# Microcontroller.net
KiCad netlist of a schematic drawn in Altium Designer
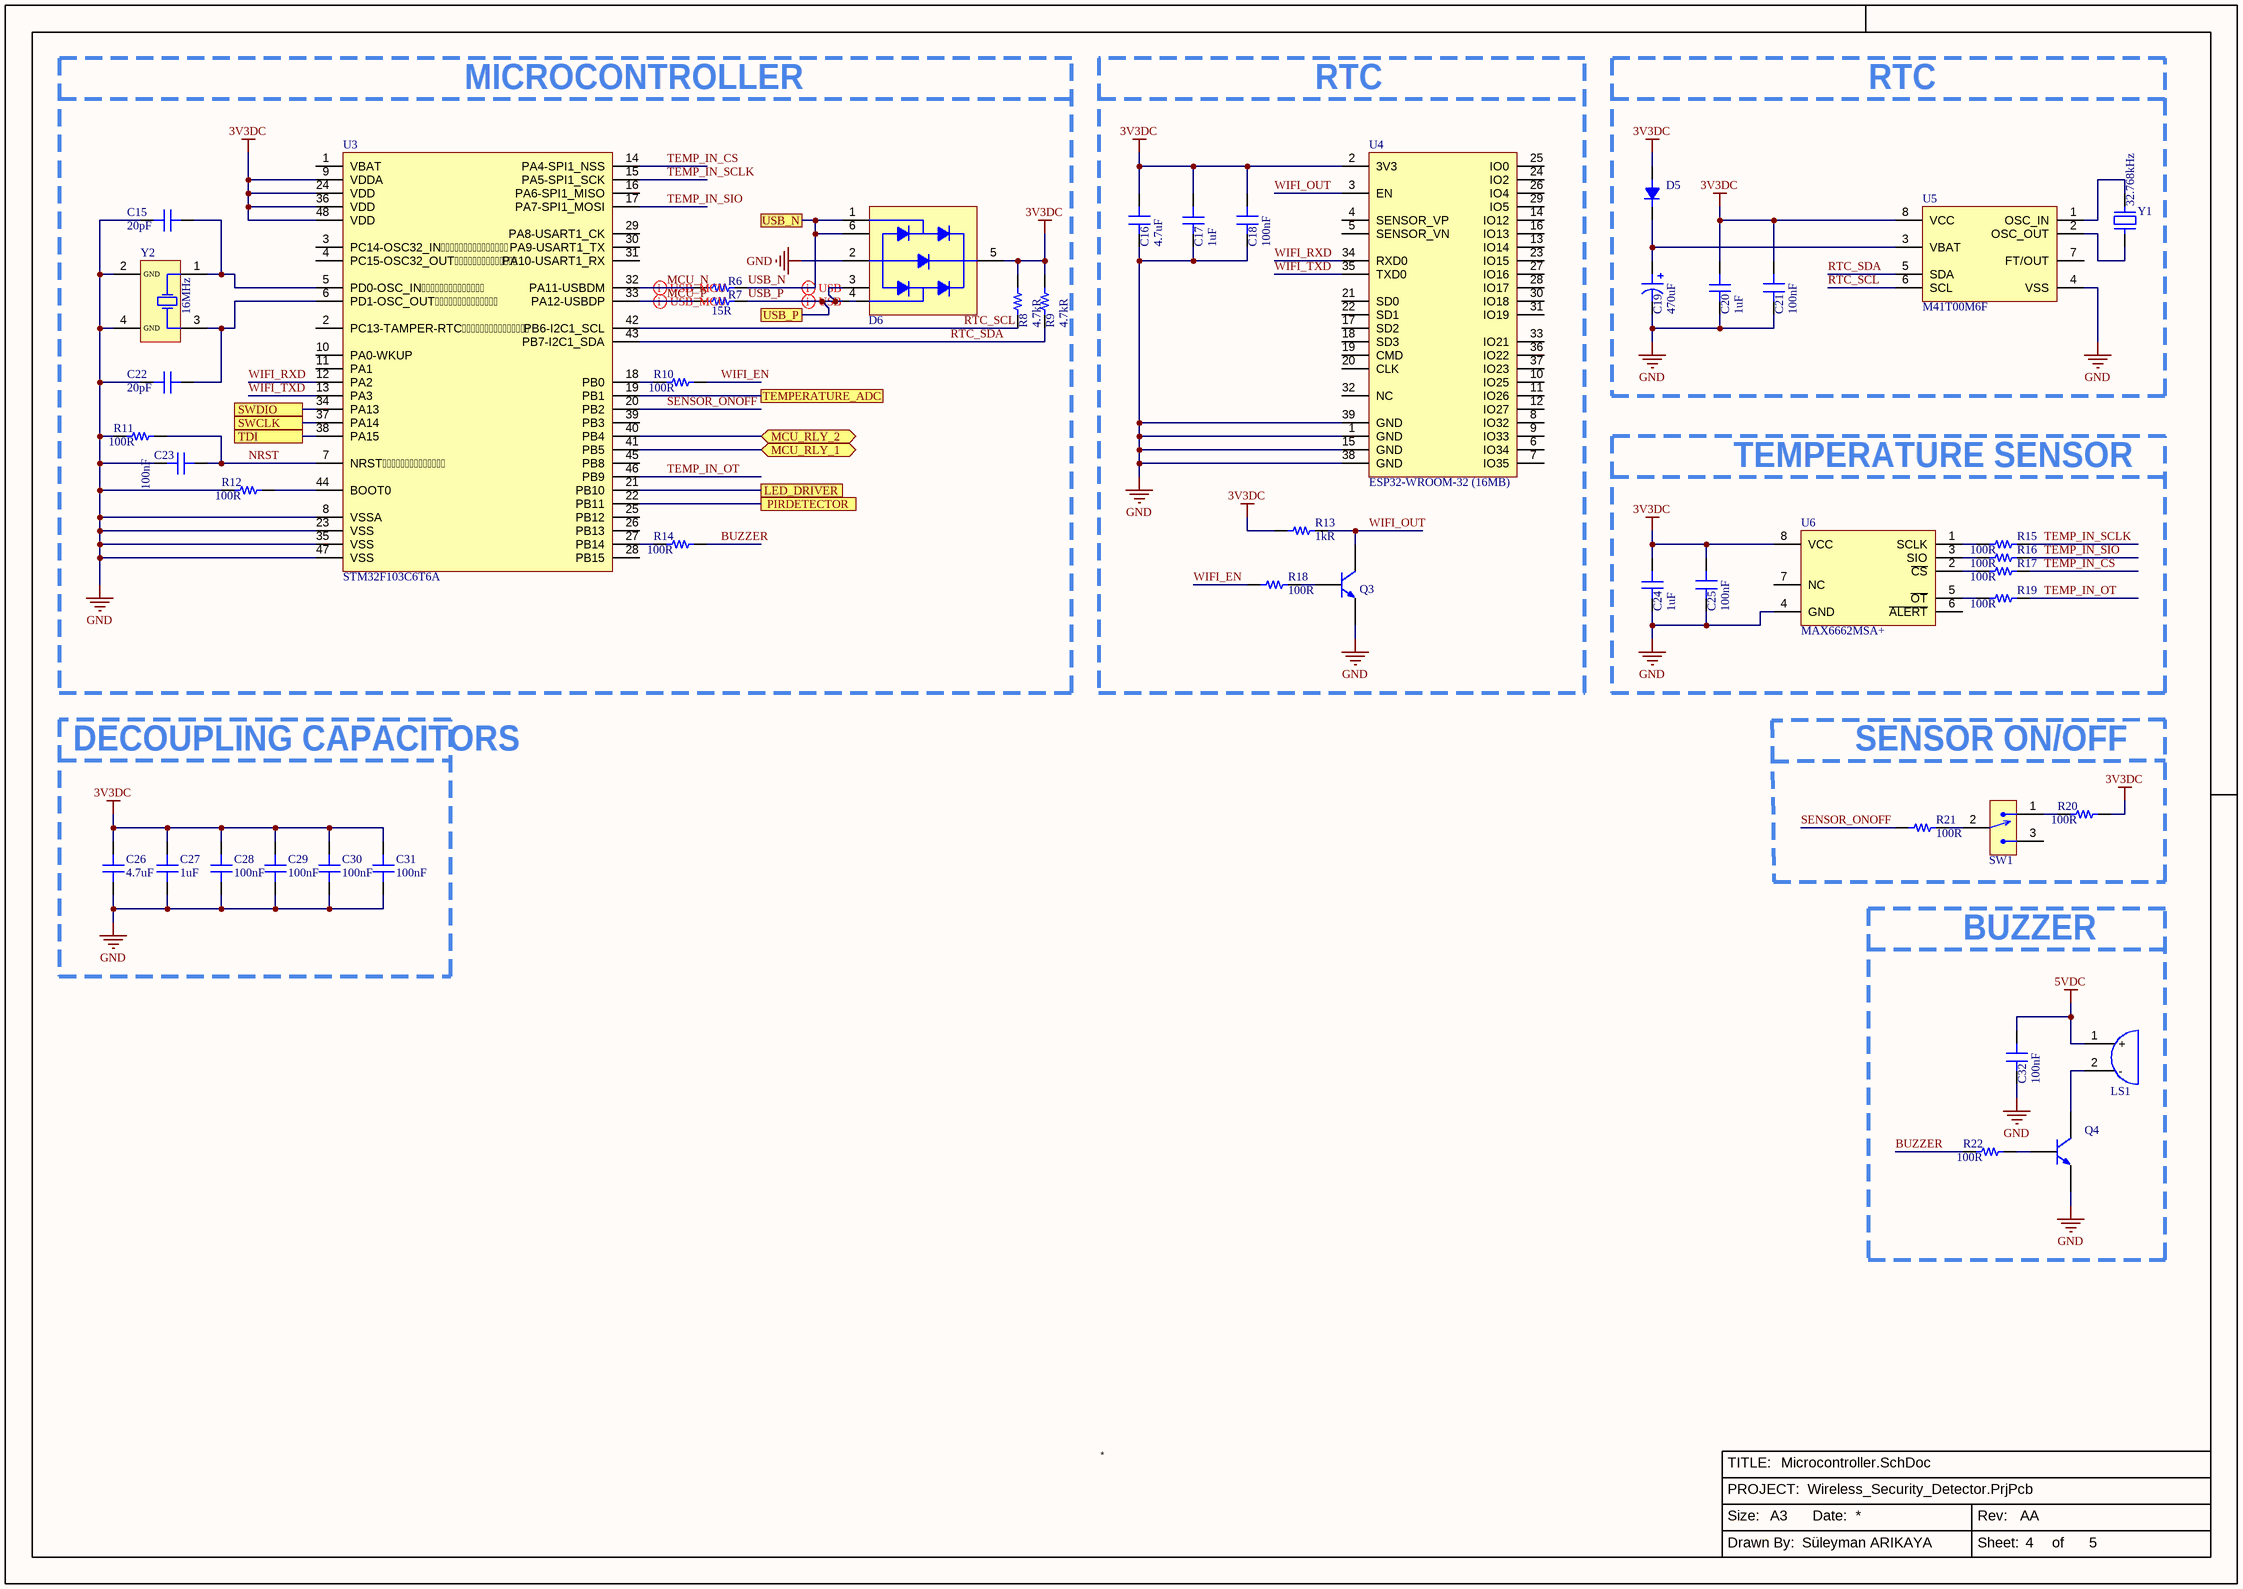
[diagram p0: Microcontroller.SchDoc]

(export (version "E")
  (design (tool "Eeschema 10.0.6"))
  (components
    (comp (ref "C15")
      (value "CL10C200JB8NNNC")
      (footprint "C0603_CER")
      (description "CAP CER 20pF %5 50V C0G/NP0 0603 SMD")
      (fields
        (field (name "MANUFACTURER") "Samsung")
        (field (name "TOLERANCE") "5%")
        (field (name "CAPACITANCE") "20pF")
        (field (name "DESIGNED BY") "Süleyman ARIKAYA")
      )
      (libsource (lib "Arikaya_Lib") (part "CAP CER 20pF 0603"))
    )
    (comp (ref "C16")
      (value "CL21A475KAQNNNE")
      (footprint "C0805_CER")
      (description "CAP CER 4.7uF %10 25V X5R 0805 SMD")
      (fields
        (field (name "MANUFACTURER") "Samsung")
        (field (name "TOLERANCE") "10%")
        (field (name "CAPACITANCE") "4.7uF")
        (field (name "DESIGNED BY") "Süleyman ARIKAYA")
      )
      (libsource (lib "Arikaya_Lib") (part "CAP CER 4.7uF 0805"))
    )
    (comp (ref "C17")
      (value "CL21B105KBFNNNE")
      (footprint "C0805_CER")
      (description "CAP CER 1uF %10 50V X7R 0805 SMD")
      (fields
        (field (name "MANUFACTURER") "Samsung")
        (field (name "TOLERANCE") "10%")
        (field (name "CAPACITANCE") "1uF")
        (field (name "DESIGNED BY") "Süleyman ARIKAYA")
      )
      (libsource (lib "Arikaya_Lib") (part "CAP CER 1uF 0805"))
    )
    (comp (ref "C18")
      (value "CL21B104KBCNNNC")
      (footprint "C0805_CER")
      (description "CAP CER 100nF %10 50V X7R 0805 SMD")
      (fields
        (field (name "MANUFACTURER") "Samsung")
        (field (name "TOLERANCE") "10%")
        (field (name "CAPACITANCE") "100nF")
        (field (name "DESIGNED BY") "Süleyman ARIKAYA")
      )
      (libsource (lib "Arikaya_Lib") (part "CAP CER 100nF 0805"))
    )
    (comp (ref "C19")
      (value "ESH477M050AH4AA")
      (footprint "CAP_RADIAL_D10_P5")
      (description "CAP ALUM 470UF 20% 50V RADIAL")
      (fields
        (field (name "MANUFACTURER") "KEMET")
        (field (name "TOLERANCE") "20%")
        (field (name "CAPACITANCE") "470uF")
        (field (name "DESIGNED BY") "Süleyman ARIKAYA")
      )
      (libsource (lib "Arikaya_Lib") (part "CAP ALU ELEC 470uF 50V"))
    )
    (comp (ref "C20")
      (value "CL21B105KBFNNNE")
      (footprint "C0805_CER")
      (description "CAP CER 1uF %10 50V X7R 0805 SMD")
      (fields
        (field (name "MANUFACTURER") "Samsung")
        (field (name "TOLERANCE") "10%")
        (field (name "CAPACITANCE") "1uF")
        (field (name "DESIGNED BY") "Süleyman ARIKAYA")
      )
      (libsource (lib "Arikaya_Lib") (part "CAP CER 1uF 0805"))
    )
    (comp (ref "C21")
      (value "CL21B104KBCNNNC")
      (footprint "C0805_CER")
      (description "CAP CER 100nF %10 50V X7R 0805 SMD")
      (fields
        (field (name "MANUFACTURER") "Samsung")
        (field (name "TOLERANCE") "10%")
        (field (name "CAPACITANCE") "100nF")
        (field (name "DESIGNED BY") "Süleyman ARIKAYA")
      )
      (libsource (lib "Arikaya_Lib") (part "CAP CER 100nF 0805"))
    )
    (comp (ref "C22")
      (value "CL10C200JB8NNNC")
      (footprint "C0603_CER")
      (description "CAP CER 20pF %5 50V C0G/NP0 0603 SMD")
      (fields
        (field (name "MANUFACTURER") "Samsung")
        (field (name "TOLERANCE") "5%")
        (field (name "CAPACITANCE") "20pF")
        (field (name "DESIGNED BY") "Süleyman ARIKAYA")
      )
      (libsource (lib "Arikaya_Lib") (part "CAP CER 20pF 0603"))
    )
    (comp (ref "C23")
      (value "C0603C104K5RAC7411")
      (footprint "C0603_CER")
      (description "CAP CER 100nF %10 50V 0603 SMD")
      (fields
        (field (name "MANUFACTURER") "KEMET")
        (field (name "TOLERANCE") "10%")
        (field (name "CAPACITANCE") "100nF")
        (field (name "DESIGNED BY") "Süleyman ARIKAYA")
      )
      (libsource (lib "Arikaya_Lib") (part "CAP CER 100nF 0603"))
    )
    (comp (ref "C24")
      (value "CL21B105KBFNNNE")
      (footprint "C0805_CER")
      (description "CAP CER 1uF %10 50V X7R 0805 SMD")
      (fields
        (field (name "MANUFACTURER") "Samsung")
        (field (name "TOLERANCE") "10%")
        (field (name "CAPACITANCE") "1uF")
        (field (name "DESIGNED BY") "Süleyman ARIKAYA")
      )
      (libsource (lib "Arikaya_Lib") (part "CAP CER 1uF 0805"))
    )
    (comp (ref "C25")
      (value "CL21B104KBCNNNC")
      (footprint "C0805_CER")
      (description "CAP CER 100nF %10 50V X7R 0805 SMD")
      (fields
        (field (name "MANUFACTURER") "Samsung")
        (field (name "TOLERANCE") "10%")
        (field (name "CAPACITANCE") "100nF")
        (field (name "DESIGNED BY") "Süleyman ARIKAYA")
      )
      (libsource (lib "Arikaya_Lib") (part "CAP CER 100nF 0805"))
    )
    (comp (ref "C26")
      (value "CL21A475KAQNNNE")
      (footprint "C0805_CER")
      (description "CAP CER 4.7uF %10 25V X5R 0805 SMD")
      (fields
        (field (name "MANUFACTURER") "Samsung")
        (field (name "TOLERANCE") "10%")
        (field (name "CAPACITANCE") "4.7uF")
        (field (name "DESIGNED BY") "Süleyman ARIKAYA")
      )
      (libsource (lib "") (part "CAP CER 4.7uF 0805_1"))
    )
    (comp (ref "C27")
      (value "CL21B105KBFNNNE")
      (footprint "C0805_CER")
      (description "CAP CER 1uF %10 50V X7R 0805 SMD")
      (fields
        (field (name "MANUFACTURER") "Samsung")
        (field (name "TOLERANCE") "10%")
        (field (name "CAPACITANCE") "1uF")
        (field (name "DESIGNED BY") "Süleyman ARIKAYA")
      )
      (libsource (lib "Arikaya_Lib") (part "CAP CER 1uF 0805"))
    )
    (comp (ref "C28")
      (value "C0603C104K5RAC7411")
      (footprint "C0603_CER")
      (description "CAP CER 100nF %10 50V 0603 SMD")
      (fields
        (field (name "MANUFACTURER") "KEMET")
        (field (name "TOLERANCE") "10%")
        (field (name "CAPACITANCE") "100nF")
        (field (name "DESIGNED BY") "Süleyman ARIKAYA")
      )
      (libsource (lib "Arikaya_Lib") (part "CAP CER 100nF 0603"))
    )
    (comp (ref "C29")
      (value "C0603C104K5RAC7411")
      (footprint "C0603_CER")
      (description "CAP CER 100nF %10 50V 0603 SMD")
      (fields
        (field (name "MANUFACTURER") "KEMET")
        (field (name "TOLERANCE") "10%")
        (field (name "CAPACITANCE") "100nF")
        (field (name "DESIGNED BY") "Süleyman ARIKAYA")
      )
      (libsource (lib "Arikaya_Lib") (part "CAP CER 100nF 0603"))
    )
    (comp (ref "C30")
      (value "C0603C104K5RAC7411")
      (footprint "C0603_CER")
      (description "CAP CER 100nF %10 50V 0603 SMD")
      (fields
        (field (name "MANUFACTURER") "KEMET")
        (field (name "TOLERANCE") "10%")
        (field (name "CAPACITANCE") "100nF")
        (field (name "DESIGNED BY") "Süleyman ARIKAYA")
      )
      (libsource (lib "Arikaya_Lib") (part "CAP CER 100nF 0603"))
    )
    (comp (ref "C31")
      (value "C0603C104K5RAC7411")
      (footprint "C0603_CER")
      (description "CAP CER 100nF %10 50V 0603 SMD")
      (fields
        (field (name "MANUFACTURER") "KEMET")
        (field (name "TOLERANCE") "10%")
        (field (name "CAPACITANCE") "100nF")
        (field (name "DESIGNED BY") "Süleyman ARIKAYA")
      )
      (libsource (lib "Arikaya_Lib") (part "CAP CER 100nF 0603"))
    )
    (comp (ref "C32")
      (value "CL21B104KBCNNNC")
      (footprint "C0805_CER")
      (description "CAP CER 100nF %10 50V X7R 0805 SMD")
      (fields
        (field (name "MANUFACTURER") "Samsung")
        (field (name "TOLERANCE") "10%")
        (field (name "CAPACITANCE") "100nF")
        (field (name "DESIGNED BY") "Süleyman ARIKAYA")
      )
      (libsource (lib "Arikaya_Lib") (part "CAP CER 100nF 0805"))
    )
    (comp (ref "D5")
      (value "1N4148WS")
      (footprint "SOD-323F")
      (description "Diode Standard 75 V 150mA Surface Mount SOD-323F VR=75V IF=150mA Trr=4ns P=200mW")
      (fields
        (field (name "MANUFACTURER") "ON Semiconductor / Fairchild")
        (field (name "DESIGNED BY") "Süleyman ARIKAYA")
      )
      (libsource (lib "Arikaya_Lib") (part "1N4148WS"))
    )
    (comp (ref "D6")
      (value "USBLC6-2SC6")
      (footprint "SOT23-6L")
      (description "TVS DIODE 5.25V 17VC SOT23-6L")
      (fields
        (field (name "MANUFACTURER") "STMicroelectronics")
        (field (name "DESIGNED BY") "Süleyman ARIKAYA")
      )
      (libsource (lib "Arikaya_Lib") (part "USB Protection TVS"))
    )
    (comp (ref "LS1")
      (value "CMI-9605IC-0580T")
      (footprint "CMI-9605IC-0580T")
      (description "Buzzers Indicator, Internally Driven Magnetic 5 V 30mA 2.7kHz 80dB @ 5V, 10cm Through Hole PC Pins")
      (fields
        (field (name "MANUFACTURER") "CUI")
        (field (name "MANUFACTURER PART NUMBER") "CMI-9605-0580T")
        (field (name "DESIGNED BY") "Süleyman ARIKAYA")
      )
      (libsource (lib "Arikaya_Lib") (part "CMI-9605IC-0580T"))
    )
    (comp (ref "Q3")
      (value "MMBT3904-7-F")
      (footprint "SOT-23F")
      (description "NPN Ic=200mA Vceo=40V hfe=100~300 fT=310MHz P=300mW SOT-23")
      (fields (field (name "MANUFACTURER") "Diodes Zetex") (field (name "DESIGNED BY") "Süleyman ARIKAYA"))
      (libsource (lib "Arikaya_Lib") (part "MMBT3904-7-F"))
    )
    (comp (ref "Q4")
      (value "MMBT3904-7-F")
      (footprint "SOT-23F")
      (description "NPN Ic=200mA Vceo=40V hfe=100~300 fT=310MHz P=300mW SOT-23")
      (fields (field (name "MANUFACTURER") "Diodes Zetex") (field (name "DESIGNED BY") "Süleyman ARIKAYA"))
      (libsource (lib "Arikaya_Lib") (part "MMBT3904-7-F"))
    )
    (comp (ref "R6")
      (value "RC0603JR-0715RL")
      (footprint "R0603")
      (description "RES 15 OHM 5% 1/10W 0603")
      (fields
        (field (name "MANUFACTURER") "Yageo")
        (field (name "TOLERANCE") "5%")
        (field (name "DESIGNED BY") "Süleyman ARIKAYA")
      )
      (libsource (lib "Arikaya_Lib") (part "RES 15 OHM 0603"))
    )
    (comp (ref "R7")
      (value "RC0603JR-0715RL")
      (footprint "R0603")
      (description "RES 15 OHM 5% 1/10W 0603")
      (fields
        (field (name "MANUFACTURER") "Yageo")
        (field (name "TOLERANCE") "5%")
        (field (name "RESISTANCE") "15R")
        (field (name "DESIGNED BY") "Süleyman ARIKAYA")
      )
      (libsource (lib "Arikaya_Lib") (part "RES 15 OHM 0603"))
    )
    (comp (ref "R8")
      (value "RC0603JR-074K7L")
      (footprint "R0603")
      (description "RES 4.7K OHM 5% 1/10W 0603")
      (fields
        (field (name "MANUFACTURER") "Yageo")
        (field (name "TOLERANCE") "5%")
        (field (name "RESISTANCE") "4.7kR")
        (field (name "DESIGNED BY") "Süleyman ARIKAYA")
      )
      (libsource (lib "Arikaya_Lib") (part "RES 4.7K OHM 0603"))
    )
    (comp (ref "R9")
      (value "RC0603JR-074K7L")
      (footprint "R0603")
      (description "RES 4.7K OHM 5% 1/10W 0603")
      (fields
        (field (name "MANUFACTURER") "Yageo")
        (field (name "TOLERANCE") "5%")
        (field (name "RESISTANCE") "4.7kR")
        (field (name "DESIGNED BY") "Süleyman ARIKAYA")
      )
      (libsource (lib "Arikaya_Lib") (part "RES 4.7K OHM 0603"))
    )
    (comp (ref "R10")
      (value "RC0603JR-07100RL")
      (footprint "R0603")
      (description "RES 100 OHM 5% 1/10W 0603")
      (fields
        (field (name "MANUFACTURER") "Yageo")
        (field (name "TOLERANCE") "5%")
        (field (name "RESISTANCE") "100R")
        (field (name "DESIGNED BY") "Süleyman ARIKAYA")
      )
      (libsource (lib "Arikaya_Lib") (part "RES 100 OHM 0603"))
    )
    (comp (ref "R11")
      (value "RC0603JR-07100RL")
      (footprint "R0603")
      (description "RES 100 OHM 5% 1/10W 0603")
      (fields
        (field (name "MANUFACTURER") "Yageo")
        (field (name "TOLERANCE") "5%")
        (field (name "RESISTANCE") "100R")
        (field (name "DESIGNED BY") "Süleyman ARIKAYA")
      )
      (libsource (lib "Arikaya_Lib") (part "RES 100 OHM 0603"))
    )
    (comp (ref "R12")
      (value "RC0603JR-07100RL")
      (footprint "R0603")
      (description "RES 100 OHM 5% 1/10W 0603")
      (fields
        (field (name "MANUFACTURER") "Yageo")
        (field (name "TOLERANCE") "5%")
        (field (name "RESISTANCE") "100R")
        (field (name "DESIGNED BY") "Süleyman ARIKAYA")
      )
      (libsource (lib "Arikaya_Lib") (part "RES 100 OHM 0603"))
    )
    (comp (ref "R13")
      (value "RC0603FR-071KL")
      (footprint "R0603")
      (description "RES SMD 1K OHM 1% 1/10W 0603")
      (fields
        (field (name "MANUFACTURER") "Yageo")
        (field (name "TOLERANCE") "1%")
        (field (name "RESISTANCE") "1kR")
        (field (name "DESIGNED BY") "Süleyman ARIKAYA")
      )
      (libsource (lib "Arikaya_Lib") (part "RES 1K OHM 0603"))
    )
    (comp (ref "R14")
      (value "RC0603JR-07100RL")
      (footprint "R0603")
      (description "RES 100 OHM 5% 1/10W 0603")
      (fields
        (field (name "MANUFACTURER") "Yageo")
        (field (name "TOLERANCE") "5%")
        (field (name "RESISTANCE") "100R")
        (field (name "DESIGNED BY") "Süleyman ARIKAYA")
      )
      (libsource (lib "Arikaya_Lib") (part "RES 100 OHM 0603"))
    )
    (comp (ref "R15")
      (value "RC0603JR-07100RL")
      (footprint "R0603")
      (description "RES 100 OHM 5% 1/10W 0603")
      (fields
        (field (name "MANUFACTURER") "Yageo")
        (field (name "TOLERANCE") "5%")
        (field (name "RESISTANCE") "100R")
        (field (name "DESIGNED BY") "Süleyman ARIKAYA")
      )
      (libsource (lib "Arikaya_Lib") (part "RES 100 OHM 0603"))
    )
    (comp (ref "R16")
      (value "RC0603JR-07100RL")
      (footprint "R0603")
      (description "RES 100 OHM 5% 1/10W 0603")
      (fields
        (field (name "MANUFACTURER") "Yageo")
        (field (name "TOLERANCE") "5%")
        (field (name "RESISTANCE") "100R")
        (field (name "DESIGNED BY") "Süleyman ARIKAYA")
      )
      (libsource (lib "Arikaya_Lib") (part "RES 100 OHM 0603"))
    )
    (comp (ref "R17")
      (value "RC0603JR-07100RL")
      (footprint "R0603")
      (description "RES 100 OHM 5% 1/10W 0603")
      (fields
        (field (name "MANUFACTURER") "Yageo")
        (field (name "TOLERANCE") "5%")
        (field (name "RESISTANCE") "100R")
        (field (name "DESIGNED BY") "Süleyman ARIKAYA")
      )
      (libsource (lib "Arikaya_Lib") (part "RES 100 OHM 0603"))
    )
    (comp (ref "R18")
      (value "RC0603JR-07100RL")
      (footprint "R0603")
      (description "RES 100 OHM 5% 1/10W 0603")
      (fields
        (field (name "MANUFACTURER") "Yageo")
        (field (name "TOLERANCE") "5%")
        (field (name "RESISTANCE") "100R")
        (field (name "DESIGNED BY") "Süleyman ARIKAYA")
      )
      (libsource (lib "Arikaya_Lib") (part "RES 100 OHM 0603"))
    )
    (comp (ref "R19")
      (value "RC0603JR-07100RL")
      (footprint "R0603")
      (description "RES 100 OHM 5% 1/10W 0603")
      (fields
        (field (name "MANUFACTURER") "Yageo")
        (field (name "TOLERANCE") "5%")
        (field (name "RESISTANCE") "100R")
        (field (name "DESIGNED BY") "Süleyman ARIKAYA")
      )
      (libsource (lib "Arikaya_Lib") (part "RES 100 OHM 0603"))
    )
    (comp (ref "R20")
      (value "RC0603JR-07100RL")
      (footprint "R0603")
      (description "RES 100 OHM 5% 1/10W 0603")
      (fields
        (field (name "MANUFACTURER") "Yageo")
        (field (name "TOLERANCE") "5%")
        (field (name "RESISTANCE") "100R")
        (field (name "DESIGNED BY") "Süleyman ARIKAYA")
      )
      (libsource (lib "Arikaya_Lib") (part "RES 100 OHM 0603"))
    )
    (comp (ref "R21")
      (value "RC0603JR-07100RL")
      (footprint "R0603")
      (description "RES 100 OHM 5% 1/10W 0603")
      (fields
        (field (name "MANUFACTURER") "Yageo")
        (field (name "TOLERANCE") "5%")
        (field (name "RESISTANCE") "100R")
        (field (name "DESIGNED BY") "Süleyman ARIKAYA")
      )
      (libsource (lib "Arikaya_Lib") (part "RES 100 OHM 0603"))
    )
    (comp (ref "R22")
      (value "RC0603JR-07100RL")
      (footprint "R0603")
      (description "RES 100 OHM 5% 1/10W 0603")
      (fields
        (field (name "MANUFACTURER") "Yageo")
        (field (name "TOLERANCE") "5%")
        (field (name "RESISTANCE") "100R")
        (field (name "DESIGNED BY") "Süleyman ARIKAYA")
      )
      (libsource (lib "Arikaya_Lib") (part "RES 100 OHM 0603"))
    )
    (comp (ref "SW1")
      (value "EG1215AA")
      (footprint "EG1215AA")
      (description "Slide Switch, SPDT, 0.025A, 24V, SMD")
      (fields
        (field (name "MANUFACTURER") "E-Switch")
        (field (name "TOLERANCE") "4.95%")
        (field (name "DESIGNED BY") "Süleyman ARIKAYA")
      )
      (libsource (lib "Arikaya_Lib") (part "EG1215AA"))
    )
    (comp (ref "U3")
      (value "STM32F103C6T6A")
      (footprint "LQFP-48")
      (description "MCU 32-bit STM32F ARM Cortex M3 RISC 32KB Flash 2.5V/3.3V 48-Pin LQFP Tray")
      (fields
        (field (name "MANUFACTURER") "STMicroelectronics")
        (field (name "DESIGNED BY") "Süleyman ARIKAYA")
      )
      (libsource (lib "Arikaya_Lib") (part "STM32F103C6T6A"))
    )
    (comp (ref "U4")
      (value "ESP32-WROOM-32 (16MB)")
      (footprint "ESP32-WROOM-32")
      (fields
        (field (name "MANUFACTURER") "Espressif Systems")
        (field (name "MANUFACTURER PART NUMBER") "ESP32-WROOM-32E(M113EH3200PH3Q0)")
        (field (name "DESIGNED BY") "Süleyman ARIKAYA")
      )
      (libsource (lib "Arikaya_Lib") (part "ESP32-WROOM-32 (16MB)"))
    )
    (comp (ref "U5")
      (value "M41T00M6F")
      (footprint "SOIC8")
      (description "Real-time Clocks Clock/Calendar I2C, 2-Wire Serial 70uA @ 2V ~ 5.5V SOIC-8_150mil RoHS")
      (fields
        (field (name "MANUFACTURER") "STMicroelectronics")
        (field (name "DESIGNED BY") "Süleyman ARIKAYA")
      )
      (libsource (lib "Arikaya_Lib") (part "M41T00M6F"))
    )
    (comp (ref "U6")
      (value "MAX6662MSA+")
      (footprint "SOIC8")
      (description "Temp Sensor Digital Serial (3-Wire, SPI) 8-Pin SOIC N Tube")
      (fields (field (name "MANUFACTURER") "Maxim") (field (name "DESIGNED BY") "Süleyman ARIKAYA"))
      (libsource (lib "Arikaya_Lib") (part "MAX6662MSA+"))
    )
    (comp (ref "Y1")
      (value "ABS05-32.768KHZ-T")
      (footprint "ABS05")
      (description "CRYSTAL 32.7680KHZ 12.5PF SMD")
      (fields
        (field (name "MANUFACTURER") "Abracon")
        (field (name "TOLERANCE") "20ppm")
        (field (name "FREQUENCY") "32.768kHz")
        (field (name "DESIGNED BY") "Süleyman ARIKAYA")
      )
      (libsource (lib "Arikaya_Lib") (part "CRYSTAL 32768kHz"))
    )
    (comp (ref "Y2")
      (value "ECS-160-20-30B-TR")
      (footprint "ECS CRYSTAL 16MHZ")
      (description "CRYSTAL 16.0000MHZ 20PF SMD")
      (fields
        (field (name "MANUFACTURER") "ECS International")
        (field (name "TOLERANCE") "50ppm")
        (field (name "FREQUENCY") "16MHz")
        (field (name "DESIGNED BY") "Süleyman ARIKAYA")
      )
      (libsource (lib "Arikaya_Lib") (part "CRYSTAL 16MHz 20pF"))
    )
  )
  (nets
    (net (code "1") (name "/BUZZER") (class "Default")
      (node (ref "R14") (pin "2") (pinfunction "2_2") (pintype "passive"))
      (node (ref "R22") (pin "1") (pinfunction "1_1") (pintype "passive"))
    )
    (net (code "2") (name "/LED_DRIVER") (class "Default")
      (node (ref "U3") (pin "21") (pinfunction "PB10_21") (pintype "passive"))
    )
    (net (code "3") (name "/MCU_N") (class "Default")
      (node (ref "R6") (pin "1") (pinfunction "1_1") (pintype "passive"))
      (node (ref "U3") (pin "32") (pinfunction "PA11-USBDM_32") (pintype "passive"))
    )
    (net (code "4") (name "/MCU_P") (class "Default")
      (node (ref "R7") (pin "1") (pinfunction "1_1") (pintype "passive"))
      (node (ref "U3") (pin "33") (pinfunction "PA12-USBDP_33") (pintype "passive"))
    )
    (net (code "5") (name "/MCU_RLY_1") (class "Default")
      (node (ref "U3") (pin "41") (pinfunction "PB5_41") (pintype "passive"))
    )
    (net (code "6") (name "/MCU_RLY_2") (class "Default")
      (node (ref "U3") (pin "40") (pinfunction "PB4_40") (pintype "passive"))
    )
    (net (code "7") (name "/NRST") (class "Default")
      (node (ref "C23") (pin "2") (pinfunction "2_2") (pintype "passive"))
      (node (ref "R11") (pin "2") (pinfunction "2_2") (pintype "passive"))
      (node (ref "U3") (pin "7") (pinfunction "NRST_7") (pintype "passive"))
    )
    (net (code "8") (name "/PIRDETECTOR") (class "Default")
      (node (ref "U3") (pin "22") (pinfunction "PB11_22") (pintype "passive"))
    )
    (net (code "9") (name "/RTC_SCL") (class "Default")
      (node (ref "R8") (pin "1") (pinfunction "1_1") (pintype "passive"))
      (node (ref "U3") (pin "42") (pinfunction "PB6-I2C1_SCL_42") (pintype "passive"))
      (node (ref "U5") (pin "6") (pinfunction "SCL_6") (pintype "passive"))
    )
    (net (code "10") (name "/RTC_SDA") (class "Default")
      (node (ref "R9") (pin "2") (pinfunction "2_2") (pintype "passive"))
      (node (ref "U3") (pin "43") (pinfunction "PB7-I2C1_SDA_43") (pintype "passive"))
      (node (ref "U5") (pin "5") (pinfunction "SDA_5") (pintype "passive"))
    )
    (net (code "11") (name "/SENSOR_ONOFF") (class "Default")
      (node (ref "R21") (pin "1") (pinfunction "1_1") (pintype "passive"))
      (node (ref "U3") (pin "20") (pinfunction "PB2_20") (pintype "passive"))
    )
    (net (code "12") (name "/SWCLK") (class "Default")
      (node (ref "U3") (pin "37") (pinfunction "PA14_37") (pintype "passive"))
    )
    (net (code "13") (name "/SWDIO") (class "Default")
      (node (ref "U3") (pin "34") (pinfunction "PA13_34") (pintype "passive"))
    )
    (net (code "14") (name "/TDI") (class "Default")
      (node (ref "U3") (pin "38") (pinfunction "PA15_38") (pintype "passive"))
    )
    (net (code "15") (name "/TEMPERATURE_ADC") (class "Default")
      (node (ref "U3") (pin "19") (pinfunction "PB1_19") (pintype "passive"))
    )
    (net (code "16") (name "/TEMP_IN_CS") (class "Default")
      (node (ref "R17") (pin "2") (pinfunction "2_2") (pintype "passive"))
      (node (ref "U3") (pin "14") (pinfunction "PA4-SPI1_NSS_14") (pintype "passive"))
    )
    (net (code "17") (name "/TEMP_IN_OT") (class "Default")
      (node (ref "R19") (pin "2") (pinfunction "2_2") (pintype "passive"))
      (node (ref "U3") (pin "46") (pinfunction "PB9_46") (pintype "passive"))
    )
    (net (code "18") (name "/TEMP_IN_SCLK") (class "Default")
      (node (ref "R15") (pin "2") (pinfunction "2_2") (pintype "passive"))
      (node (ref "U3") (pin "15") (pinfunction "PA5-SPI1_SCK_15") (pintype "passive"))
    )
    (net (code "19") (name "/TEMP_IN_SIO") (class "Default")
      (node (ref "R16") (pin "2") (pinfunction "2_2") (pintype "passive"))
      (node (ref "U3") (pin "17") (pinfunction "PA7-SPI1_MOSI_17") (pintype "passive"))
    )
    (net (code "20") (name "/USB_N") (class "Default")
      (node (ref "D6") (pin "1") (pinfunction "I/O1_1") (pintype "passive"))
      (node (ref "D6") (pin "6") (pinfunction "I/O1_6") (pintype "passive"))
      (node (ref "R6") (pin "2") (pinfunction "2_2") (pintype "passive"))
    )
    (net (code "21") (name "/USB_P") (class "Default")
      (node (ref "D6") (pin "3") (pinfunction "I/O2_3") (pintype "passive"))
      (node (ref "D6") (pin "4") (pinfunction "I/O2_4") (pintype "passive"))
      (node (ref "R7") (pin "2") (pinfunction "2_2") (pintype "passive"))
    )
    (net (code "22") (name "/WIFI_EN") (class "Default")
      (node (ref "R10") (pin "2") (pinfunction "2_2") (pintype "passive"))
      (node (ref "R18") (pin "1") (pinfunction "1_1") (pintype "passive"))
    )
    (net (code "23") (name "/WIFI_OUT") (class "Default")
      (node (ref "Q3") (pin "3") (pinfunction "C_3") (pintype "passive"))
      (node (ref "R13") (pin "2") (pinfunction "2_2") (pintype "passive"))
      (node (ref "U4") (pin "3") (pinfunction "EN_3") (pintype "passive"))
    )
    (net (code "24") (name "/WIFI_RXD") (class "Default")
      (node (ref "U3") (pin "12") (pinfunction "PA2_12") (pintype "passive"))
      (node (ref "U4") (pin "34") (pinfunction "RXD0_34") (pintype "passive"))
    )
    (net (code "25") (name "/WIFI_TXD") (class "Default")
      (node (ref "U3") (pin "13") (pinfunction "PA3_13") (pintype "passive"))
      (node (ref "U4") (pin "35") (pinfunction "TXD0_35") (pintype "passive"))
    )
    (net (code "26") (name "3V3DC") (class "Default")
      (node (ref "C16") (pin "2") (pinfunction "2_2") (pintype "passive"))
      (node (ref "C17") (pin "2") (pinfunction "2_2") (pintype "passive"))
      (node (ref "C18") (pin "2") (pinfunction "2_2") (pintype "passive"))
      (node (ref "C20") (pin "2") (pinfunction "2_2") (pintype "passive"))
      (node (ref "C21") (pin "2") (pinfunction "2_2") (pintype "passive"))
      (node (ref "C24") (pin "2") (pinfunction "2_2") (pintype "passive"))
      (node (ref "C25") (pin "2") (pinfunction "2_2") (pintype "passive"))
      (node (ref "C26") (pin "2") (pinfunction "2_2") (pintype "passive"))
      (node (ref "C27") (pin "2") (pinfunction "2_2") (pintype "passive"))
      (node (ref "C28") (pin "2") (pinfunction "2_2") (pintype "passive"))
      (node (ref "C29") (pin "2") (pinfunction "2_2") (pintype "passive"))
      (node (ref "C30") (pin "2") (pinfunction "2_2") (pintype "passive"))
      (node (ref "C31") (pin "2") (pinfunction "2_2") (pintype "passive"))
      (node (ref "D5") (pin "A") (pinfunction "A_A") (pintype "passive"))
      (node (ref "D6") (pin "5") (pinfunction "VBUS_5") (pintype "passive"))
      (node (ref "R13") (pin "1") (pinfunction "1_1") (pintype "passive"))
      (node (ref "R20") (pin "2") (pinfunction "2_2") (pintype "passive"))
      (node (ref "R8") (pin "2") (pinfunction "2_2") (pintype "passive"))
      (node (ref "R9") (pin "1") (pinfunction "1_1") (pintype "passive"))
      (node (ref "U3") (pin "24") (pinfunction "VDD_24") (pintype "passive"))
      (node (ref "U3") (pin "36") (pinfunction "VDD_36") (pintype "passive"))
      (node (ref "U3") (pin "48") (pinfunction "VDD_48") (pintype "passive"))
      (node (ref "U3") (pin "9") (pinfunction "VDDA_9") (pintype "passive"))
      (node (ref "U4") (pin "2") (pinfunction "3V3_2") (pintype "passive"))
      (node (ref "U5") (pin "8") (pinfunction "VCC_8") (pintype "passive"))
      (node (ref "U6") (pin "8") (pinfunction "VCC_8") (pintype "passive"))
    )
    (net (code "27") (name "5VDC") (class "Default")
      (node (ref "C32") (pin "2") (pinfunction "2_2") (pintype "passive"))
      (node (ref "LS1") (pin "1") (pinfunction "+_1") (pintype "passive"))
    )
    (net (code "28") (name "GND") (class "Default")
      (node (ref "C15") (pin "1") (pinfunction "1_1") (pintype "passive"))
      (node (ref "C16") (pin "1") (pinfunction "1_1") (pintype "passive"))
      (node (ref "C17") (pin "1") (pinfunction "1_1") (pintype "passive"))
      (node (ref "C18") (pin "1") (pinfunction "1_1") (pintype "passive"))
      (node (ref "C19") (pin "2") (pinfunction "2_2") (pintype "passive"))
      (node (ref "C20") (pin "1") (pinfunction "1_1") (pintype "passive"))
      (node (ref "C21") (pin "1") (pinfunction "1_1") (pintype "passive"))
      (node (ref "C22") (pin "1") (pinfunction "1_1") (pintype "passive"))
      (node (ref "C23") (pin "1") (pinfunction "1_1") (pintype "passive"))
      (node (ref "C24") (pin "1") (pinfunction "1_1") (pintype "passive"))
      (node (ref "C25") (pin "1") (pinfunction "1_1") (pintype "passive"))
      (node (ref "C26") (pin "1") (pinfunction "1_1") (pintype "passive"))
      (node (ref "C27") (pin "1") (pinfunction "1_1") (pintype "passive"))
      (node (ref "C28") (pin "1") (pinfunction "1_1") (pintype "passive"))
      (node (ref "C29") (pin "1") (pinfunction "1_1") (pintype "passive"))
      (node (ref "C30") (pin "1") (pinfunction "1_1") (pintype "passive"))
      (node (ref "C31") (pin "1") (pinfunction "1_1") (pintype "passive"))
      (node (ref "C32") (pin "1") (pinfunction "1_1") (pintype "passive"))
      (node (ref "D6") (pin "2") (pinfunction "GND_2") (pintype "passive"))
      (node (ref "Q3") (pin "2") (pinfunction "E_2") (pintype "passive"))
      (node (ref "Q4") (pin "2") (pinfunction "E_2") (pintype "passive"))
      (node (ref "R11") (pin "1") (pinfunction "1_1") (pintype "passive"))
      (node (ref "R12") (pin "1") (pinfunction "1_1") (pintype "passive"))
      (node (ref "U3") (pin "23") (pinfunction "VSS_23") (pintype "passive"))
      (node (ref "U3") (pin "35") (pinfunction "VSS_35") (pintype "passive"))
      (node (ref "U3") (pin "47") (pinfunction "VSS_47") (pintype "passive"))
      (node (ref "U3") (pin "8") (pinfunction "VSSA_8") (pintype "passive"))
      (node (ref "U4") (pin "1") (pinfunction "GND_1") (pintype "passive"))
      (node (ref "U4") (pin "15") (pinfunction "GND_15") (pintype "passive"))
      (node (ref "U4") (pin "38") (pinfunction "GND_38") (pintype "passive"))
      (node (ref "U4") (pin "39") (pinfunction "GND_39") (pintype "passive"))
      (node (ref "U5") (pin "4") (pinfunction "VSS_4") (pintype "passive"))
      (node (ref "U6") (pin "4") (pinfunction "GND_4") (pintype "passive"))
      (node (ref "Y2") (pin "2") (pinfunction "GND_2") (pintype "power_in"))
      (node (ref "Y2") (pin "4") (pinfunction "GND_4") (pintype "passive"))
    )
    (net (code "29") (name "Net-(LS1--)") (class "Default")
      (node (ref "LS1") (pin "2") (pinfunction "-_2") (pintype "passive"))
      (node (ref "Q4") (pin "3") (pinfunction "C_3") (pintype "passive"))
    )
    (net (code "30") (name "Net-(Q3-B)") (class "Default")
      (node (ref "Q3") (pin "1") (pinfunction "B_1") (pintype "passive"))
      (node (ref "R18") (pin "2") (pinfunction "2_2") (pintype "passive"))
    )
    (net (code "31") (name "Net-(Q4-B)") (class "Default")
      (node (ref "Q4") (pin "1") (pinfunction "B_1") (pintype "passive"))
      (node (ref "R22") (pin "2") (pinfunction "2_2") (pintype "passive"))
    )
    (net (code "32") (name "Net-(R20-Pad1)") (class "Default")
      (node (ref "R20") (pin "1") (pinfunction "1_1") (pintype "passive"))
      (node (ref "SW1") (pin "1") (pinfunction "1_1") (pintype "passive"))
    )
    (net (code "33") (name "Net-(R21-Pad2)") (class "Default")
      (node (ref "R21") (pin "2") (pinfunction "2_2") (pintype "passive"))
      (node (ref "SW1") (pin "2") (pinfunction "2_2") (pintype "passive"))
    )
    (net (code "34") (name "Net-(U3-BOOT0)") (class "Default")
      (node (ref "R12") (pin "2") (pinfunction "2_2") (pintype "passive"))
      (node (ref "U3") (pin "44") (pinfunction "BOOT0_44") (pintype "passive"))
    )
    (net (code "35") (name "Net-(U3-PB0)") (class "Default")
      (node (ref "R10") (pin "1") (pinfunction "1_1") (pintype "passive"))
      (node (ref "U3") (pin "18") (pinfunction "PB0_18") (pintype "passive"))
    )
    (net (code "36") (name "Net-(U3-PB14)") (class "Default")
      (node (ref "R14") (pin "1") (pinfunction "1_1") (pintype "passive"))
      (node (ref "U3") (pin "27") (pinfunction "PB14_27") (pintype "passive"))
    )
    (net (code "37") (name "Net-(U3-PD0-OSC_IN)") (class "Default")
      (node (ref "C15") (pin "2") (pinfunction "2_2") (pintype "passive"))
      (node (ref "U3") (pin "5") (pinfunction "PD0-OSC_IN_5") (pintype "passive"))
      (node (ref "Y2") (pin "1") (pinfunction "IN/OUT_1") (pintype "passive"))
    )
    (net (code "38") (name "Net-(U3-PD1-OSC_OUT)") (class "Default")
      (node (ref "C22") (pin "2") (pinfunction "2_2") (pintype "passive"))
      (node (ref "U3") (pin "6") (pinfunction "PD1-OSC_OUT_6") (pintype "passive"))
      (node (ref "Y2") (pin "3") (pinfunction "OUT/IN_3") (pintype "passive"))
    )
    (net (code "39") (name "Net-(U5-OSC_IN)") (class "Default")
      (node (ref "U5") (pin "1") (pinfunction "OSC_IN_1") (pintype "passive"))
      (node (ref "Y1") (pin "2") (pinfunction "2_2") (pintype "passive"))
    )
    (net (code "40") (name "Net-(U5-OSC_OUT)") (class "Default")
      (node (ref "U5") (pin "2") (pinfunction "OSC_OUT_2") (pintype "passive"))
      (node (ref "Y1") (pin "1") (pinfunction "1_1") (pintype "passive"))
    )
    (net (code "41") (name "Net-(U5-VBAT)") (class "Default")
      (node (ref "C19") (pin "1") (pinfunction "1_1") (pintype "passive"))
      (node (ref "D5") (pin "C") (pinfunction "C_C") (pintype "passive"))
      (node (ref "U5") (pin "3") (pinfunction "VBAT_3") (pintype "passive"))
    )
    (net (code "42") (name "Net-(U6-SCLK)") (class "Default")
      (node (ref "R15") (pin "1") (pinfunction "1_1") (pintype "passive"))
      (node (ref "U6") (pin "1") (pinfunction "SCLK_1") (pintype "passive"))
    )
    (net (code "43") (name "Net-(U6-SIO)") (class "Default")
      (node (ref "R16") (pin "1") (pinfunction "1_1") (pintype "passive"))
      (node (ref "U6") (pin "3") (pinfunction "SIO_3") (pintype "passive"))
    )
    (net (code "44") (name "Net-(U6-~{CS})") (class "Default")
      (node (ref "R17") (pin "1") (pinfunction "1_1") (pintype "passive"))
      (node (ref "U6") (pin "2") (pinfunction "~{CS}_2") (pintype "passive"))
    )
    (net (code "45") (name "Net-(U6-~{OT})") (class "Default")
      (node (ref "R19") (pin "1") (pinfunction "1_1") (pintype "passive"))
      (node (ref "U6") (pin "5") (pinfunction "~{OT}_5") (pintype "passive"))
    )
    (net (code "46") (name "unconnected-(SW1-Pad3)") (class "Default")
      (node (ref "SW1") (pin "3") (pinfunction "3_3") (pintype "passive"))
    )
    (net (code "47") (name "unconnected-(U3-PA0-WKUP-Pad10)") (class "Default")
      (node (ref "U3") (pin "10") (pinfunction "PA0-WKUP_10") (pintype "passive"))
    )
    (net (code "48") (name "unconnected-(U3-PA1-Pad11)") (class "Default")
      (node (ref "U3") (pin "11") (pinfunction "PA1_11") (pintype "passive"))
    )
    (net (code "49") (name "unconnected-(U3-PA6-SPI1_MISO-Pad16)") (class "Default")
      (node (ref "U3") (pin "16") (pinfunction "PA6-SPI1_MISO_16") (pintype "passive"))
    )
    (net (code "50") (name "unconnected-(U3-PA8-USART1_CK-Pad29)") (class "Default")
      (node (ref "U3") (pin "29") (pinfunction "PA8-USART1_CK_29") (pintype "passive"))
    )
    (net (code "51") (name "unconnected-(U3-PA9-USART1_TX-Pad30)") (class "Default")
      (node (ref "U3") (pin "30") (pinfunction "PA9-USART1_TX_30") (pintype "passive"))
    )
    (net (code "52") (name "unconnected-(U3-PA10-USART1_RX-Pad31)") (class "Default")
      (node (ref "U3") (pin "31") (pinfunction "PA10-USART1_RX_31") (pintype "passive"))
    )
    (net (code "53") (name "unconnected-(U3-PB3-Pad39)") (class "Default")
      (node (ref "U3") (pin "39") (pinfunction "PB3_39") (pintype "passive"))
    )
    (net (code "54") (name "unconnected-(U3-PB8-Pad45)") (class "Default")
      (node (ref "U3") (pin "45") (pinfunction "PB8_45") (pintype "passive"))
    )
    (net (code "55") (name "unconnected-(U3-PB12-Pad25)") (class "Default")
      (node (ref "U3") (pin "25") (pinfunction "PB12_25") (pintype "passive"))
    )
    (net (code "56") (name "unconnected-(U3-PB13-Pad26)") (class "Default")
      (node (ref "U3") (pin "26") (pinfunction "PB13_26") (pintype "passive"))
    )
    (net (code "57") (name "unconnected-(U3-PB15-Pad28)") (class "Default")
      (node (ref "U3") (pin "28") (pinfunction "PB15_28") (pintype "passive"))
    )
    (net (code "58") (name "unconnected-(U3-PC13-TAMPER-RTC-Pad2)") (class "Default")
      (node (ref "U3") (pin "2") (pinfunction "PC13-TAMPER-RTC_2") (pintype "passive"))
    )
    (net (code "59") (name "unconnected-(U3-PC14-OSC32_IN-Pad3)") (class "Default")
      (node (ref "U3") (pin "3") (pinfunction "PC14-OSC32_IN_3") (pintype "passive"))
    )
    (net (code "60") (name "unconnected-(U3-PC15-OSC32_OUT-Pad4)") (class "Default")
      (node (ref "U3") (pin "4") (pinfunction "PC15-OSC32_OUT_4") (pintype "passive"))
    )
    (net (code "61") (name "unconnected-(U3-VBAT-Pad1)") (class "Default")
      (node (ref "U3") (pin "1") (pinfunction "VBAT_1") (pintype "passive"))
    )
    (net (code "62") (name "unconnected-(U4-CLK-Pad20)") (class "Default")
      (node (ref "U4") (pin "20") (pinfunction "CLK_20") (pintype "passive"))
    )
    (net (code "63") (name "unconnected-(U4-CMD-Pad19)") (class "Default")
      (node (ref "U4") (pin "19") (pinfunction "CMD_19") (pintype "passive"))
    )
    (net (code "64") (name "unconnected-(U4-IO0-Pad25)") (class "Default")
      (node (ref "U4") (pin "25") (pinfunction "IO0_25") (pintype "passive"))
    )
    (net (code "65") (name "unconnected-(U4-IO2-Pad24)") (class "Default")
      (node (ref "U4") (pin "24") (pinfunction "IO2_24") (pintype "passive"))
    )
    (net (code "66") (name "unconnected-(U4-IO4-Pad26)") (class "Default")
      (node (ref "U4") (pin "26") (pinfunction "IO4_26") (pintype "passive"))
    )
    (net (code "67") (name "unconnected-(U4-IO5-Pad29)") (class "Default")
      (node (ref "U4") (pin "29") (pinfunction "IO5_29") (pintype "passive"))
    )
    (net (code "68") (name "unconnected-(U4-IO12-Pad14)") (class "Default")
      (node (ref "U4") (pin "14") (pinfunction "IO12_14") (pintype "passive"))
    )
    (net (code "69") (name "unconnected-(U4-IO13-Pad16)") (class "Default")
      (node (ref "U4") (pin "16") (pinfunction "IO13_16") (pintype "passive"))
    )
    (net (code "70") (name "unconnected-(U4-IO14-Pad13)") (class "Default")
      (node (ref "U4") (pin "13") (pinfunction "IO14_13") (pintype "passive"))
    )
    (net (code "71") (name "unconnected-(U4-IO15-Pad23)") (class "Default")
      (node (ref "U4") (pin "23") (pinfunction "IO15_23") (pintype "passive"))
    )
    (net (code "72") (name "unconnected-(U4-IO16-Pad27)") (class "Default")
      (node (ref "U4") (pin "27") (pinfunction "IO16_27") (pintype "passive"))
    )
    (net (code "73") (name "unconnected-(U4-IO17-Pad28)") (class "Default")
      (node (ref "U4") (pin "28") (pinfunction "IO17_28") (pintype "passive"))
    )
    (net (code "74") (name "unconnected-(U4-IO18-Pad30)") (class "Default")
      (node (ref "U4") (pin "30") (pinfunction "IO18_30") (pintype "passive"))
    )
    (net (code "75") (name "unconnected-(U4-IO19-Pad31)") (class "Default")
      (node (ref "U4") (pin "31") (pinfunction "IO19_31") (pintype "passive"))
    )
    (net (code "76") (name "unconnected-(U4-IO21-Pad33)") (class "Default")
      (node (ref "U4") (pin "33") (pinfunction "IO21_33") (pintype "passive"))
    )
    (net (code "77") (name "unconnected-(U4-IO22-Pad36)") (class "Default")
      (node (ref "U4") (pin "36") (pinfunction "IO22_36") (pintype "passive"))
    )
    (net (code "78") (name "unconnected-(U4-IO23-Pad37)") (class "Default")
      (node (ref "U4") (pin "37") (pinfunction "IO23_37") (pintype "passive"))
    )
    (net (code "79") (name "unconnected-(U4-IO25-Pad10)") (class "Default")
      (node (ref "U4") (pin "10") (pinfunction "IO25_10") (pintype "passive"))
    )
    (net (code "80") (name "unconnected-(U4-IO26-Pad11)") (class "Default")
      (node (ref "U4") (pin "11") (pinfunction "IO26_11") (pintype "passive"))
    )
    (net (code "81") (name "unconnected-(U4-IO27-Pad12)") (class "Default")
      (node (ref "U4") (pin "12") (pinfunction "IO27_12") (pintype "passive"))
    )
    (net (code "82") (name "unconnected-(U4-IO32-Pad8)") (class "Default")
      (node (ref "U4") (pin "8") (pinfunction "IO32_8") (pintype "passive"))
    )
    (net (code "83") (name "unconnected-(U4-IO33-Pad9)") (class "Default")
      (node (ref "U4") (pin "9") (pinfunction "IO33_9") (pintype "passive"))
    )
    (net (code "84") (name "unconnected-(U4-IO34-Pad6)") (class "Default")
      (node (ref "U4") (pin "6") (pinfunction "IO34_6") (pintype "passive"))
    )
    (net (code "85") (name "unconnected-(U4-IO35-Pad7)") (class "Default")
      (node (ref "U4") (pin "7") (pinfunction "IO35_7") (pintype "passive"))
    )
    (net (code "86") (name "unconnected-(U4-NC-Pad32)") (class "Default")
      (node (ref "U4") (pin "32") (pinfunction "NC_32") (pintype "passive"))
    )
    (net (code "87") (name "unconnected-(U4-SD0-Pad21)") (class "Default")
      (node (ref "U4") (pin "21") (pinfunction "SD0_21") (pintype "passive"))
    )
    (net (code "88") (name "unconnected-(U4-SD1-Pad22)") (class "Default")
      (node (ref "U4") (pin "22") (pinfunction "SD1_22") (pintype "passive"))
    )
    (net (code "89") (name "unconnected-(U4-SD2-Pad17)") (class "Default")
      (node (ref "U4") (pin "17") (pinfunction "SD2_17") (pintype "passive"))
    )
    (net (code "90") (name "unconnected-(U4-SD3-Pad18)") (class "Default")
      (node (ref "U4") (pin "18") (pinfunction "SD3_18") (pintype "passive"))
    )
    (net (code "91") (name "unconnected-(U4-SENSOR_VN-Pad5)") (class "Default")
      (node (ref "U4") (pin "5") (pinfunction "SENSOR_VN_5") (pintype "passive"))
    )
    (net (code "92") (name "unconnected-(U4-SENSOR_VP-Pad4)") (class "Default")
      (node (ref "U4") (pin "4") (pinfunction "SENSOR_VP_4") (pintype "passive"))
    )
    (net (code "93") (name "unconnected-(U5-FT{slash}OUT-Pad7)") (class "Default")
      (node (ref "U5") (pin "7") (pinfunction "FT/OUT_7") (pintype "passive"))
    )
    (net (code "94") (name "unconnected-(U6-NC-Pad7)") (class "Default")
      (node (ref "U6") (pin "7") (pinfunction "NC_7") (pintype "passive"))
    )
    (net (code "95") (name "unconnected-(U6-~{ALERT}-Pad6)") (class "Default")
      (node (ref "U6") (pin "6") (pinfunction "~{ALERT}_6") (pintype "passive"))
    )
  )
)
